# MOSFETs.net
KiCad netlist of a schematic drawn in Altium Designer
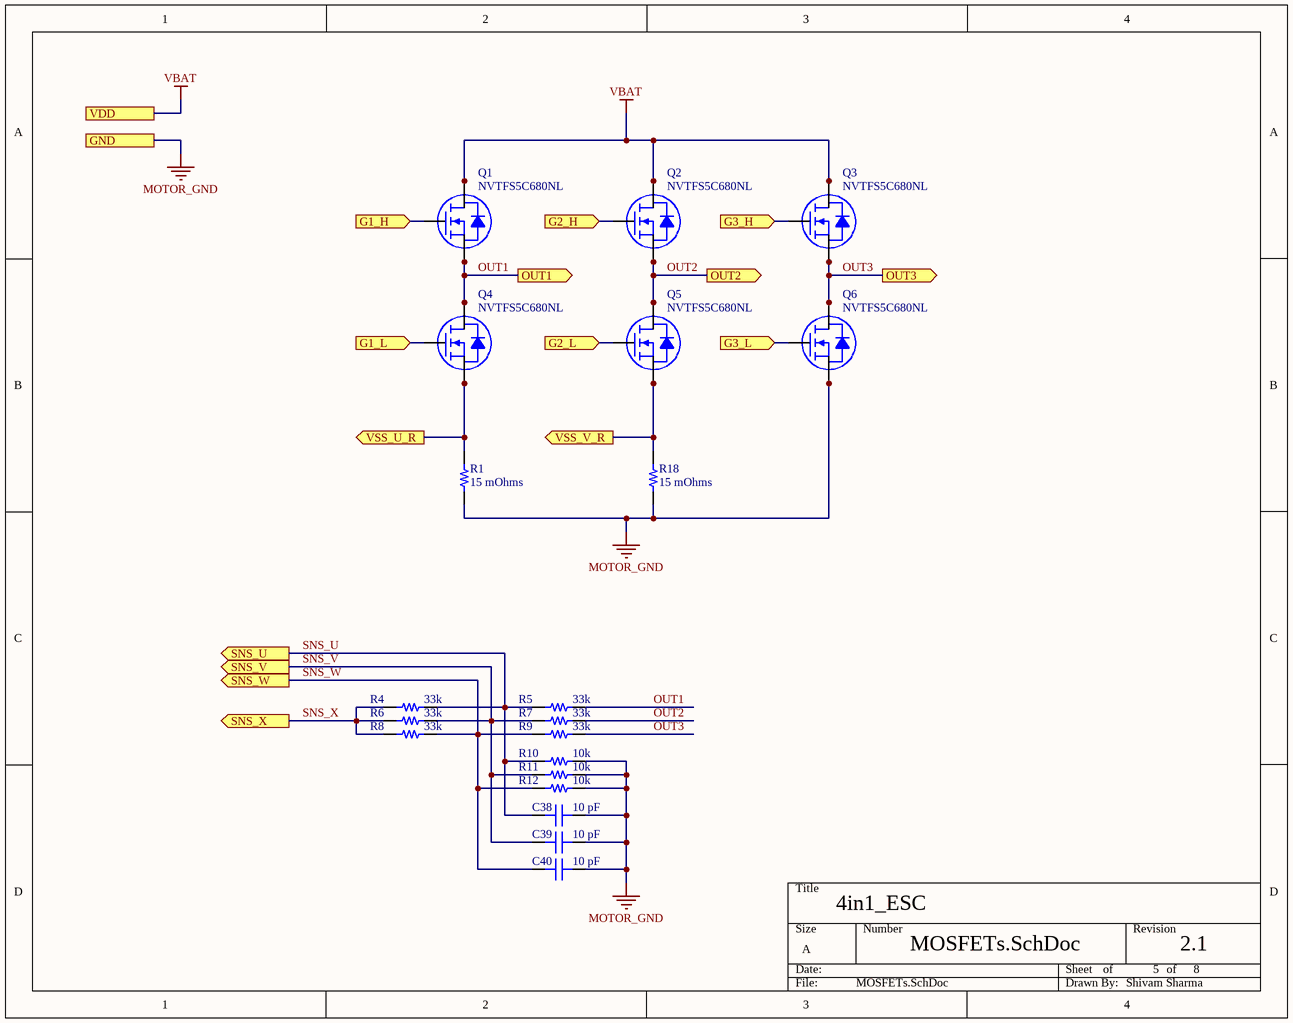
[diagram p0: MOSFETs.SchDoc]

(export (version "E")
  (design (tool "Eeschema 10.0.6"))
  (components
    (comp (ref "C38")
      (value "10 pF")
      (footprint "CAP 0201_0603")
      (description "CAP CER 0.1UF 35V X5R 0201")
      (fields
        (field (name "PART NUMBER") "GRT033R6YA104KE01D")
        (field (name "MANUFACTURER") "Murata Electronics")
      )
      (libsource (lib "Celestial Altium Library - altium_library") (part "Capacitor"))
    )
    (comp (ref "C39")
      (value "10 pF")
      (footprint "CAP 0201_0603")
      (description "CAP CER 0.1UF 35V X5R 0201")
      (fields
        (field (name "PART NUMBER") "GRT033R6YA104KE01D")
        (field (name "MANUFACTURER") "Murata Electronics")
      )
      (libsource (lib "Celestial Altium Library - altium_library") (part "Capacitor"))
    )
    (comp (ref "C40")
      (value "10 pF")
      (footprint "CAP 0201_0603")
      (description "CAP CER 0.1UF 35V X5R 0201")
      (fields
        (field (name "PART NUMBER") "GRT033R6YA104KE01D")
        (field (name "MANUFACTURER") "Murata Electronics")
      )
      (libsource (lib "Celestial Altium Library - altium_library") (part "Capacitor"))
    )
    (comp (ref "Q1")
      (value "NVTFS5C680NL")
      (footprint "NVTFS015N04CTAG")
      (description "N-FET")
      (libsource (lib "IC") (part "NVTFS5C680NL"))
    )
    (comp (ref "Q2")
      (value "NVTFS5C680NL")
      (footprint "NVTFS015N04CTAG")
      (description "N-FET")
      (libsource (lib "IC") (part "NVTFS5C680NL"))
    )
    (comp (ref "Q3")
      (value "NVTFS5C680NL")
      (footprint "NVTFS015N04CTAG")
      (description "N-FET")
      (libsource (lib "IC") (part "NVTFS5C680NL"))
    )
    (comp (ref "Q4")
      (value "NVTFS5C680NL")
      (footprint "NVTFS015N04CTAG")
      (description "N-FET")
      (libsource (lib "IC") (part "NVTFS5C680NL"))
    )
    (comp (ref "Q5")
      (value "NVTFS5C680NL")
      (footprint "NVTFS015N04CTAG")
      (description "N-FET")
      (libsource (lib "IC") (part "NVTFS5C680NL"))
    )
    (comp (ref "Q6")
      (value "NVTFS5C680NL")
      (footprint "NVTFS015N04CTAG")
      (description "N-FET")
      (libsource (lib "IC") (part "NVTFS5C680NL"))
    )
    (comp (ref "R1")
      (value "15 mOhms")
      (footprint "RES 0805_2012")
      (description "RES SMD 20K OHM 0.1% 1W 0805")
      (fields
        (field (name "PART NUMBER") "PCAN0805E2002BST5")
        (field (name "MANUFACTURER") "Vishay Thin Film")
      )
      (libsource (lib "Celestial Altium Library - altium_library") (part "Resistor"))
    )
    (comp (ref "R4")
      (value "33k")
      (footprint "RES 0201_0603")
      (description "RES SMD 10K OHM 1% 1/20W 0201")
      (fields (field (name "PART NUMBER") "CRCW020110K0FKED") (field (name "MANUFACTURER") "Vishay Dale"))
      (libsource (lib "Celestial Altium Library - altium_library") (part "Resistor"))
    )
    (comp (ref "R5")
      (value "33k")
      (footprint "RES 0201_0603")
      (description "RES SMD 10K OHM 1% 1/20W 0201")
      (fields (field (name "PART NUMBER") "CRCW020110K0FKED") (field (name "MANUFACTURER") "Vishay Dale"))
      (libsource (lib "Celestial Altium Library - altium_library") (part "Resistor"))
    )
    (comp (ref "R6")
      (value "33k")
      (footprint "RES 0201_0603")
      (description "RES SMD 10K OHM 1% 1/20W 0201")
      (fields (field (name "PART NUMBER") "CRCW020110K0FKED") (field (name "MANUFACTURER") "Vishay Dale"))
      (libsource (lib "Celestial Altium Library - altium_library") (part "Resistor"))
    )
    (comp (ref "R7")
      (value "33k")
      (footprint "RES 0201_0603")
      (description "RES SMD 10K OHM 1% 1/20W 0201")
      (fields (field (name "PART NUMBER") "CRCW020110K0FKED") (field (name "MANUFACTURER") "Vishay Dale"))
      (libsource (lib "Celestial Altium Library - altium_library") (part "Resistor"))
    )
    (comp (ref "R8")
      (value "33k")
      (footprint "RES 0201_0603")
      (description "RES SMD 10K OHM 1% 1/20W 0201")
      (fields (field (name "PART NUMBER") "CRCW020110K0FKED") (field (name "MANUFACTURER") "Vishay Dale"))
      (libsource (lib "Celestial Altium Library - altium_library") (part "Resistor"))
    )
    (comp (ref "R9")
      (value "33k")
      (footprint "RES 0201_0603")
      (description "RES SMD 10K OHM 1% 1/20W 0201")
      (fields (field (name "PART NUMBER") "CRCW020110K0FKED") (field (name "MANUFACTURER") "Vishay Dale"))
      (libsource (lib "Celestial Altium Library - altium_library") (part "Resistor"))
    )
    (comp (ref "R10")
      (value "10k")
      (footprint "RES 0201_0603")
      (description "RES SMD 10K OHM 1% 1/20W 0201")
      (fields (field (name "PART NUMBER") "CRCW020110K0FKED") (field (name "MANUFACTURER") "Vishay Dale"))
      (libsource (lib "Celestial Altium Library - altium_library") (part "Resistor"))
    )
    (comp (ref "R11")
      (value "10k")
      (footprint "RES 0201_0603")
      (description "RES SMD 10K OHM 1% 1/20W 0201")
      (fields (field (name "PART NUMBER") "CRCW020110K0FKED") (field (name "MANUFACTURER") "Vishay Dale"))
      (libsource (lib "Celestial Altium Library - altium_library") (part "Resistor"))
    )
    (comp (ref "R12")
      (value "10k")
      (footprint "RES 0201_0603")
      (description "RES SMD 10K OHM 1% 1/20W 0201")
      (fields (field (name "PART NUMBER") "CRCW020110K0FKED") (field (name "MANUFACTURER") "Vishay Dale"))
      (libsource (lib "Celestial Altium Library - altium_library") (part "Resistor"))
    )
    (comp (ref "R18")
      (value "15 mOhms")
      (footprint "RES 0805_2012")
      (description "RES SMD 20K OHM 0.1% 1W 0805")
      (fields
        (field (name "PART NUMBER") "PCAN0805E2002BST5")
        (field (name "MANUFACTURER") "Vishay Thin Film")
      )
      (libsource (lib "Celestial Altium Library - altium_library") (part "Resistor"))
    )
  )
  (nets
    (net (code "1") (name "/G1_H") (class "Default")
      (node (ref "Q1") (pin "4") (pinfunction "G_4") (pintype "passive"))
    )
    (net (code "2") (name "/G1_L") (class "Default")
      (node (ref "Q4") (pin "4") (pinfunction "G_4") (pintype "passive"))
    )
    (net (code "3") (name "/G2_H") (class "Default")
      (node (ref "Q2") (pin "4") (pinfunction "G_4") (pintype "passive"))
    )
    (net (code "4") (name "/G2_L") (class "Default")
      (node (ref "Q5") (pin "4") (pinfunction "G_4") (pintype "passive"))
    )
    (net (code "5") (name "/G3_H") (class "Default")
      (node (ref "Q3") (pin "4") (pinfunction "G_4") (pintype "passive"))
    )
    (net (code "6") (name "/G3_L") (class "Default")
      (node (ref "Q6") (pin "4") (pinfunction "G_4") (pintype "passive"))
    )
    (net (code "7") (name "/OUT1") (class "Default")
      (node (ref "Q1") (pin "1") (pinfunction "S_1") (pintype "passive"))
      (node (ref "Q1") (pin "2") (pinfunction "S_2") (pintype "passive"))
      (node (ref "Q1") (pin "3") (pinfunction "S_3") (pintype "passive"))
      (node (ref "Q4") (pin "5") (pinfunction "D_5") (pintype "passive"))
      (node (ref "Q4") (pin "6") (pinfunction "D_6") (pintype "passive"))
      (node (ref "Q4") (pin "7") (pinfunction "D_7") (pintype "passive"))
      (node (ref "Q4") (pin "8") (pinfunction "D_8") (pintype "passive"))
      (node (ref "R5") (pin "2") (pinfunction "2_2") (pintype "passive"))
    )
    (net (code "8") (name "/OUT2") (class "Default")
      (node (ref "Q2") (pin "1") (pinfunction "S_1") (pintype "passive"))
      (node (ref "Q2") (pin "2") (pinfunction "S_2") (pintype "passive"))
      (node (ref "Q2") (pin "3") (pinfunction "S_3") (pintype "passive"))
      (node (ref "Q5") (pin "5") (pinfunction "D_5") (pintype "passive"))
      (node (ref "Q5") (pin "6") (pinfunction "D_6") (pintype "passive"))
      (node (ref "Q5") (pin "7") (pinfunction "D_7") (pintype "passive"))
      (node (ref "Q5") (pin "8") (pinfunction "D_8") (pintype "passive"))
      (node (ref "R7") (pin "2") (pinfunction "2_2") (pintype "passive"))
    )
    (net (code "9") (name "/OUT3") (class "Default")
      (node (ref "Q3") (pin "1") (pinfunction "S_1") (pintype "passive"))
      (node (ref "Q3") (pin "2") (pinfunction "S_2") (pintype "passive"))
      (node (ref "Q3") (pin "3") (pinfunction "S_3") (pintype "passive"))
      (node (ref "Q6") (pin "5") (pinfunction "D_5") (pintype "passive"))
      (node (ref "Q6") (pin "6") (pinfunction "D_6") (pintype "passive"))
      (node (ref "Q6") (pin "7") (pinfunction "D_7") (pintype "passive"))
      (node (ref "Q6") (pin "8") (pinfunction "D_8") (pintype "passive"))
      (node (ref "R9") (pin "2") (pinfunction "2_2") (pintype "passive"))
    )
    (net (code "10") (name "/SNS_U") (class "Default")
      (node (ref "C38") (pin "1") (pinfunction "1_1") (pintype "passive"))
      (node (ref "R10") (pin "1") (pinfunction "1_1") (pintype "passive"))
      (node (ref "R4") (pin "2") (pinfunction "2_2") (pintype "passive"))
      (node (ref "R5") (pin "1") (pinfunction "1_1") (pintype "passive"))
    )
    (net (code "11") (name "/SNS_V") (class "Default")
      (node (ref "C39") (pin "1") (pinfunction "1_1") (pintype "passive"))
      (node (ref "R11") (pin "1") (pinfunction "1_1") (pintype "passive"))
      (node (ref "R6") (pin "2") (pinfunction "2_2") (pintype "passive"))
      (node (ref "R7") (pin "1") (pinfunction "1_1") (pintype "passive"))
    )
    (net (code "12") (name "/SNS_W") (class "Default")
      (node (ref "C40") (pin "1") (pinfunction "1_1") (pintype "passive"))
      (node (ref "R12") (pin "1") (pinfunction "1_1") (pintype "passive"))
      (node (ref "R8") (pin "2") (pinfunction "2_2") (pintype "passive"))
      (node (ref "R9") (pin "1") (pinfunction "1_1") (pintype "passive"))
    )
    (net (code "13") (name "/SNS_X") (class "Default")
      (node (ref "R4") (pin "1") (pinfunction "1_1") (pintype "passive"))
      (node (ref "R6") (pin "1") (pinfunction "1_1") (pintype "passive"))
      (node (ref "R8") (pin "1") (pinfunction "1_1") (pintype "passive"))
    )
    (net (code "14") (name "/VSS_U_R") (class "Default")
      (node (ref "Q4") (pin "1") (pinfunction "S_1") (pintype "passive"))
      (node (ref "Q4") (pin "2") (pinfunction "S_2") (pintype "passive"))
      (node (ref "Q4") (pin "3") (pinfunction "S_3") (pintype "passive"))
      (node (ref "R1") (pin "2") (pinfunction "2_2") (pintype "passive"))
    )
    (net (code "15") (name "/VSS_V_R") (class "Default")
      (node (ref "Q5") (pin "1") (pinfunction "S_1") (pintype "passive"))
      (node (ref "Q5") (pin "2") (pinfunction "S_2") (pintype "passive"))
      (node (ref "Q5") (pin "3") (pinfunction "S_3") (pintype "passive"))
      (node (ref "R18") (pin "2") (pinfunction "2_2") (pintype "passive"))
    )
    (net (code "16") (name "MOTOR_GND") (class "Default")
      (node (ref "C38") (pin "2") (pinfunction "2_2") (pintype "passive"))
      (node (ref "C39") (pin "2") (pinfunction "2_2") (pintype "passive"))
      (node (ref "C40") (pin "2") (pinfunction "2_2") (pintype "passive"))
      (node (ref "Q6") (pin "1") (pinfunction "S_1") (pintype "passive"))
      (node (ref "Q6") (pin "2") (pinfunction "S_2") (pintype "passive"))
      (node (ref "Q6") (pin "3") (pinfunction "S_3") (pintype "passive"))
      (node (ref "R1") (pin "1") (pinfunction "1_1") (pintype "passive"))
      (node (ref "R10") (pin "2") (pinfunction "2_2") (pintype "passive"))
      (node (ref "R11") (pin "2") (pinfunction "2_2") (pintype "passive"))
      (node (ref "R12") (pin "2") (pinfunction "2_2") (pintype "passive"))
      (node (ref "R18") (pin "1") (pinfunction "1_1") (pintype "passive"))
    )
    (net (code "17") (name "VBAT") (class "Default")
      (node (ref "Q1") (pin "5") (pinfunction "D_5") (pintype "passive"))
      (node (ref "Q1") (pin "6") (pinfunction "D_6") (pintype "passive"))
      (node (ref "Q1") (pin "7") (pinfunction "D_7") (pintype "passive"))
      (node (ref "Q1") (pin "8") (pinfunction "D_8") (pintype "passive"))
      (node (ref "Q2") (pin "5") (pinfunction "D_5") (pintype "passive"))
      (node (ref "Q2") (pin "6") (pinfunction "D_6") (pintype "passive"))
      (node (ref "Q2") (pin "7") (pinfunction "D_7") (pintype "passive"))
      (node (ref "Q2") (pin "8") (pinfunction "D_8") (pintype "passive"))
      (node (ref "Q3") (pin "5") (pinfunction "D_5") (pintype "passive"))
      (node (ref "Q3") (pin "6") (pinfunction "D_6") (pintype "passive"))
      (node (ref "Q3") (pin "7") (pinfunction "D_7") (pintype "passive"))
      (node (ref "Q3") (pin "8") (pinfunction "D_8") (pintype "passive"))
    )
  )
)
